# Enclosure_85x58_BHWSL.net
KiCad netlist of a schematic drawn in EAGLE
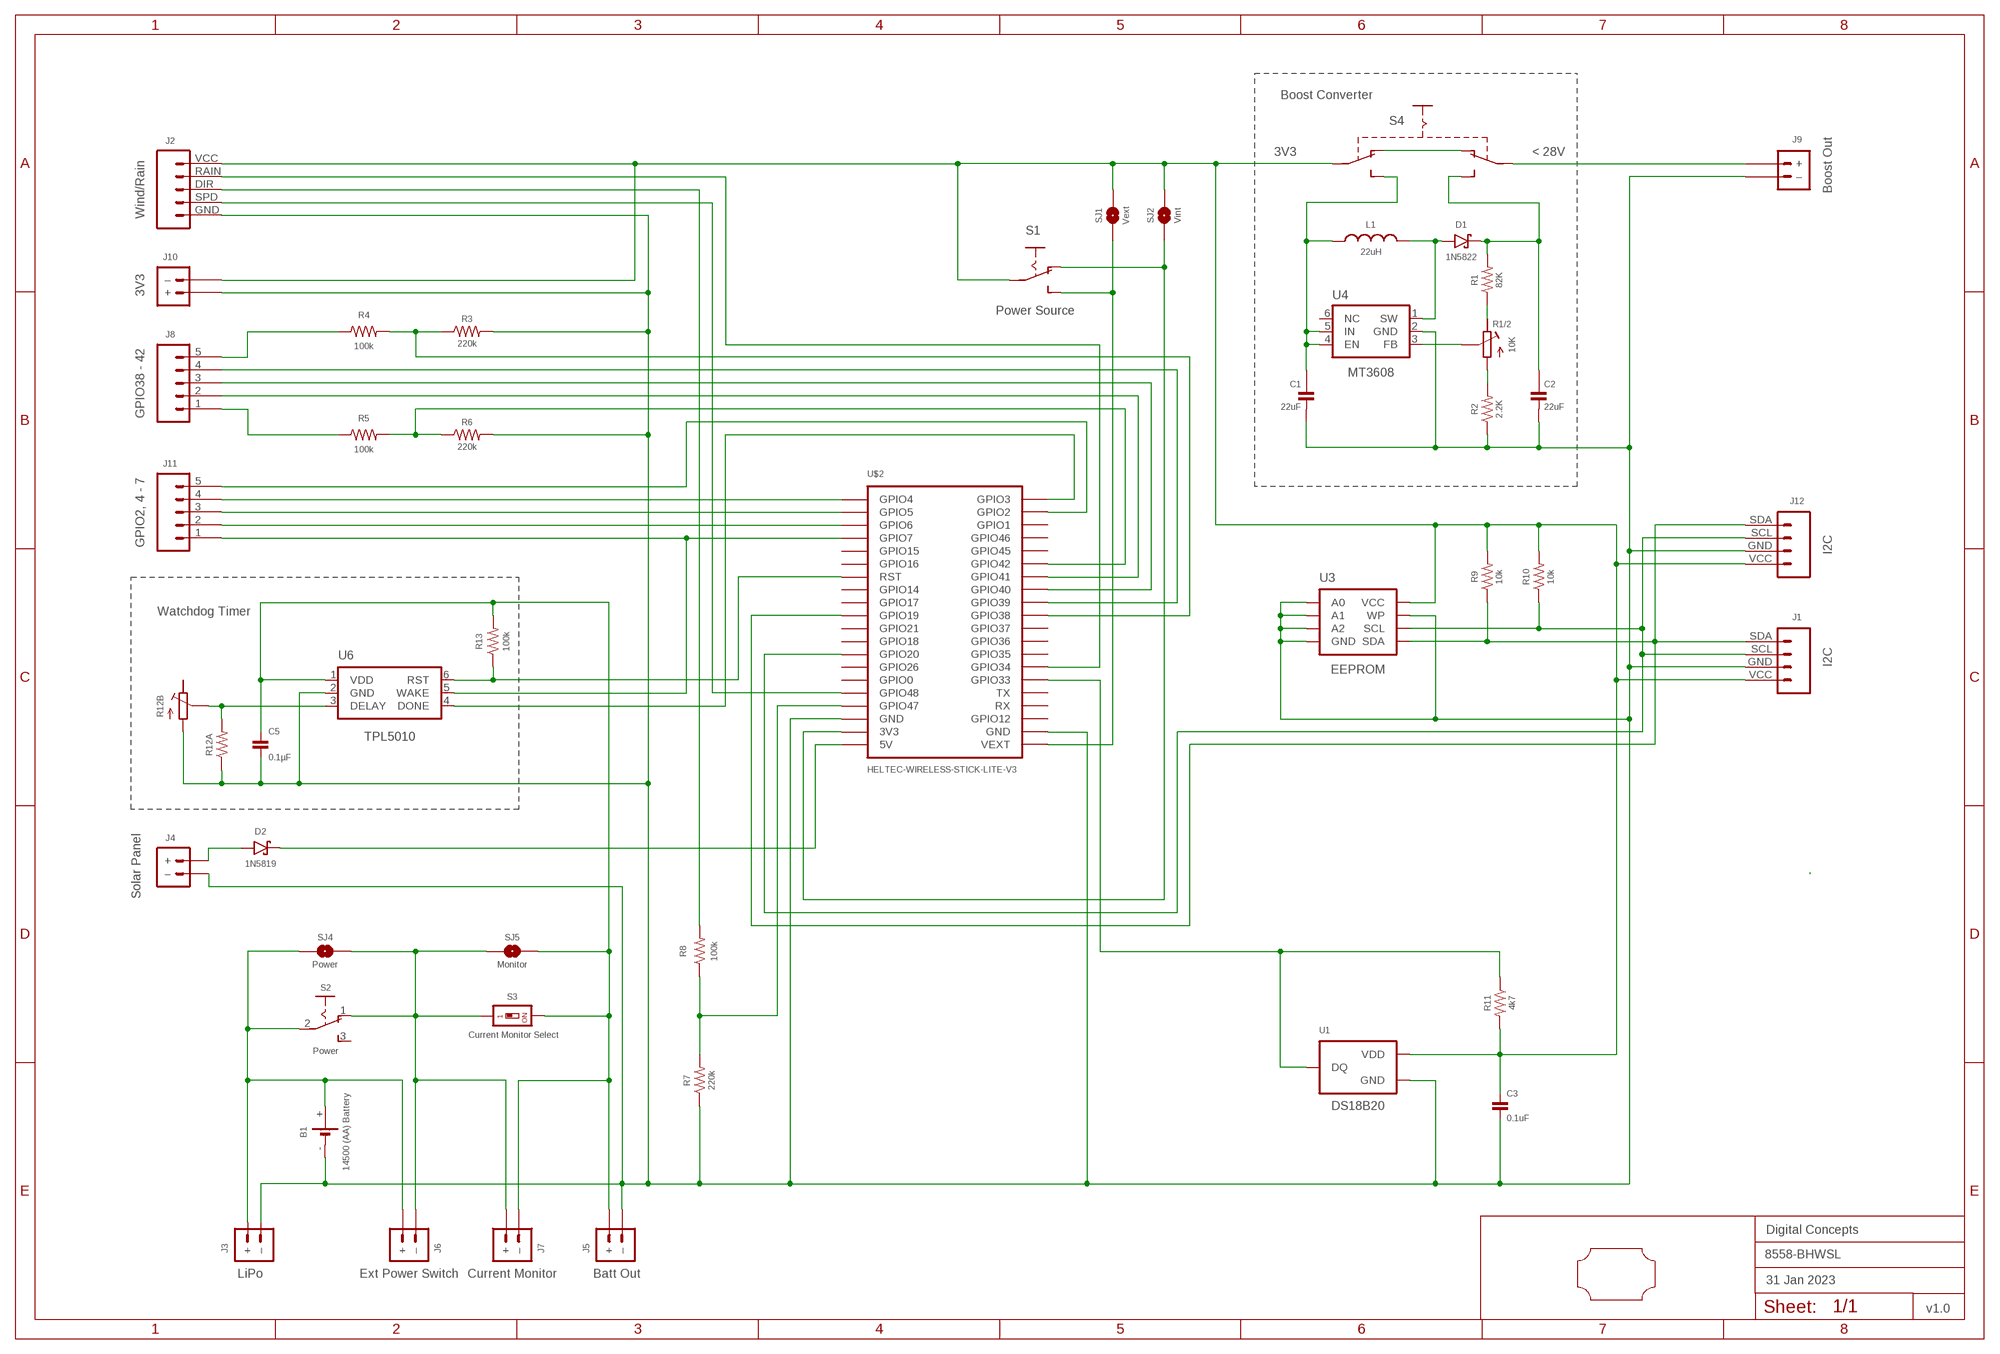
[diagram p0: schematic, sheet 1]

(export (version "E")
  (design (tool "Eeschema 10.0.6"))
  (components
    (comp (ref "B1")
      (value "14500 (AA) Battery")
      (footprint "eagle-import:BATTERY-14500")
      (libsource (lib "eagle-import") (part "BATTERY-HOLDER-14500(AA)"))
    )
    (comp (ref "C1")
      (value "22uF")
      (footprint "eagle-import:C1206")
      (libsource (lib "eagle-import") (part "CAPACITOR-1206"))
    )
    (comp (ref "C2")
      (value "22uF")
      (footprint "eagle-import:C1206")
      (libsource (lib "eagle-import") (part "CAPACITOR-1206"))
    )
    (comp (ref "C3")
      (value "0.1uF")
      (footprint "eagle-import:C0805")
      (libsource (lib "eagle-import") (part "CAPACITOR-0805"))
    )
    (comp (ref "C5")
      (value "0.1µF")
      (footprint "eagle-import:C0805")
      (libsource (lib "eagle-import") (part "CAPACITOR-0805"))
    )
    (comp (ref "D1")
      (value "1N5822")
      (footprint "eagle-import:DIODE_SMB")
      (libsource (lib "eagle-import") (part "DIODE-SCHOTTKY-1N5822"))
    )
    (comp (ref "D2")
      (value "1N5819")
      (footprint "eagle-import:SOD-123")
      (libsource (lib "eagle-import") (part "1N5819-SOD-123"))
    )
    (comp (ref "J1")
      (value "I2C")
      (footprint "eagle-import:JST-PH2.0-4-VERTICAL-I2C")
      (libsource (lib "eagle-import") (part "JST-PH2.0-4-VERTICAL-I2C"))
    )
    (comp (ref "J2")
      (value "Wind/Rain")
      (footprint "eagle-import:JST-PH2.0-5-WEATHER")
      (libsource (lib "eagle-import") (part "JST-PH2.0-5-VERTICAL-WEATHER"))
    )
    (comp (ref "J3")
      (value "LiPo")
      (footprint "eagle-import:JST-PH2.0-2-HORIZONTAL")
      (libsource (lib "eagle-import") (part "JST-PH2.0-2-MALE-HORIZONTALJST-PTH-2"))
    )
    (comp (ref "J4")
      (value "Solar Panel")
      (footprint "eagle-import:JST-PH2.0-2-DUAL-POWER")
      (libsource (lib "eagle-import") (part "JST-PH2.0-2-DUAL-POWERJST-PTH-2"))
    )
    (comp (ref "J5")
      (value "Batt Out")
      (footprint "eagle-import:JST-GH1.25-2-HORIZONTAL")
      (libsource (lib "eagle-import") (part "JST-GH1.25-2-HORIZONTAL-POWER"))
    )
    (comp (ref "J6")
      (value "Ext Power Switch")
      (footprint "eagle-import:JST-PH2.0-2-DUAL-POWER")
      (libsource (lib "eagle-import") (part "JST-PH2.0-2-DUAL-POWERJST-PTH-2"))
    )
    (comp (ref "J7")
      (value "Current Monitor")
      (footprint "eagle-import:JST-PH2.0-2-HORIZONTAL-POWER@1")
      (libsource (lib "eagle-import") (part "JST-PH2.0-2-HORIZONTAL-POWERJST-PTH-2"))
    )
    (comp (ref "J8")
      (value "GPIO38 - 42")
      (footprint "eagle-import:JST-PH2.0-5-HORIZONTAL")
      (libsource (lib "eagle-import") (part "JST-PH2.0-5-HORIZONTAL"))
    )
    (comp (ref "J9")
      (value "Boost Out")
      (footprint "eagle-import:JST-PH2.0-2-HORIZONTAL-POWER")
      (libsource (lib "eagle-import") (part "JST-PH2.0-2-H-POWER"))
    )
    (comp (ref "J10")
      (value "3V3")
      (footprint "eagle-import:JST-PH2.0-2-HORIZONTAL-POWER")
      (libsource (lib "eagle-import") (part "JST-PH2.0-2-H-POWER"))
    )
    (comp (ref "J11")
      (value "GPIO2, 4 - 7")
      (footprint "eagle-import:JST-PH2.0-5-HORIZONTAL")
      (libsource (lib "eagle-import") (part "JST-PH2.0-5-HORIZONTAL"))
    )
    (comp (ref "J12")
      (value "I2C")
      (footprint "eagle-import:JST-PH2.0-4-HORIZONTAL-I2C")
      (libsource (lib "eagle-import") (part "JST-PH2.0-4-HORIZONTAL-I2C"))
    )
    (comp (ref "L1")
      (value "22uH")
      (footprint "eagle-import:CDRH104R+6D28")
      (libsource (lib "eagle-import") (part "INDUCTOR-CDRH104R/6D28L5038P"))
    )
    (comp (ref "R1")
      (value "82K")
      (footprint "eagle-import:R0805")
      (libsource (lib "eagle-import") (part "RESISTORR0805"))
    )
    (comp (ref "R1/2")
      (value "10K")
      (footprint "eagle-import:RTRIM64P")
      (libsource (lib "eagle-import") (part "RESISTOR-TRIMM-BAOTER-HORIZONTAL"))
    )
    (comp (ref "R2")
      (value "2.2K")
      (footprint "eagle-import:R0805")
      (libsource (lib "eagle-import") (part "RESISTORR0805"))
    )
    (comp (ref "R3")
      (value "220k")
      (footprint "eagle-import:R0805")
      (libsource (lib "eagle-import") (part "RESISTORR0805"))
    )
    (comp (ref "R4")
      (value "100k")
      (footprint "eagle-import:R0805")
      (libsource (lib "eagle-import") (part "RESISTORR0805"))
    )
    (comp (ref "R5")
      (value "100k")
      (footprint "eagle-import:R0805")
      (libsource (lib "eagle-import") (part "RESISTORR0805"))
    )
    (comp (ref "R6")
      (value "220k")
      (footprint "eagle-import:R0805")
      (libsource (lib "eagle-import") (part "RESISTORR0805"))
    )
    (comp (ref "R7")
      (value "220k")
      (footprint "eagle-import:R0805")
      (libsource (lib "eagle-import") (part "RESISTORR0805"))
    )
    (comp (ref "R8")
      (value "100k")
      (footprint "eagle-import:R0805")
      (libsource (lib "eagle-import") (part "RESISTORR0805"))
    )
    (comp (ref "R9")
      (value "10k")
      (footprint "eagle-import:R0805")
      (libsource (lib "eagle-import") (part "RESISTORR0805"))
    )
    (comp (ref "R10")
      (value "10k")
      (footprint "eagle-import:R0805")
      (libsource (lib "eagle-import") (part "RESISTORR0805"))
    )
    (comp (ref "R11")
      (value "4k7")
      (footprint "eagle-import:R0805")
      (libsource (lib "eagle-import") (part "RESISTORR0805"))
    )
    (comp (ref "R12A")
      (value "RESISTORR0805")
      (footprint "eagle-import:R0805")
      (libsource (lib "eagle-import") (part "RESISTORR0805"))
    )
    (comp (ref "R12B")
      (value "RESISTOR-TRIMM-33")
      (footprint "eagle-import:RTRIM3_3")
      (libsource (lib "eagle-import") (part "RESISTOR-TRIMM-33"))
    )
    (comp (ref "R13")
      (value "100k")
      (footprint "eagle-import:R0805")
      (libsource (lib "eagle-import") (part "RESISTORR0805"))
    )
    (comp (ref "S1")
      (value "Power Source")
      (footprint "eagle-import:SWITCH-SPDT-SMT")
      (libsource (lib "eagle-import") (part "SWITCH-SLIDE-SPDT-SMT"))
    )
    (comp (ref "S2")
      (value "Power")
      (footprint "eagle-import:SWITCH-SLIDE-SPDT")
      (libsource (lib "eagle-import") (part "SWITCH-SLIDE-SPDT"))
    )
    (comp (ref "S3")
      (value "Current Monitor Select")
      (footprint "eagle-import:SMD-001")
      (libsource (lib "eagle-import") (part "SWITCH-DIP-SWS001"))
    )
    (comp (ref "S4")
      (value "SWITCH-SLIDE-DPDT-PTH-S")
      (footprint "eagle-import:SWITCH-DPDT-PTH")
      (libsource (lib "eagle-import") (part "SWITCH-SLIDE-DPDT-PTH-S"))
    )
    (comp (ref "SJ1")
      (value "Vext")
      (footprint "eagle-import:SJ")
      (libsource (lib "eagle-import") (part "SJ"))
    )
    (comp (ref "SJ2")
      (value "Vint")
      (footprint "eagle-import:SJ-VIA-1")
      (libsource (lib "eagle-import") (part "SJ-V-1"))
    )
    (comp (ref "SJ4")
      (value "Power")
      (footprint "eagle-import:SJ")
      (libsource (lib "eagle-import") (part "SJ"))
    )
    (comp (ref "SJ5")
      (value "Monitor")
      (footprint "eagle-import:SJ")
      (libsource (lib "eagle-import") (part "SJ"))
    )
    (comp (ref "U$1")
      (value "PCB-OUTLINE-85X58")
      (footprint "eagle-import:PROTO-28X18-OUTLINE")
      (libsource (lib "eagle-import") (part "PCB-OUTLINE-85X58"))
    )
    (comp (ref "U$2")
      (value "HELTEC-WIRELESS-STICK-LITE-V3")
      (footprint "eagle-import:HELTEC-WIRELESS-STICK-LITE-V3")
      (libsource (lib "eagle-import") (part "HELTEC-WIRELESS-STICK-LITE-V3"))
    )
    (comp (ref "U1")
      (value "DS18B20")
      (footprint "eagle-import:TO-92")
      (fields (field (name "MF") "Maxim Integrated"))
      (libsource (lib "eagle-import") (part "THERMOMETER-DS18B20"))
    )
    (comp (ref "U3")
      (value "EEPROM")
      (footprint "eagle-import:SOP-8")
      (libsource (lib "eagle-import") (part "AT24CXX-EEPROM"))
    )
    (comp (ref "U4")
      (value "MT3608")
      (footprint "eagle-import:SOT-23-6@1")
      (libsource (lib "eagle-import") (part "MT3608"))
    )
    (comp (ref "U6")
      (value "TPL5010")
      (footprint "eagle-import:SOT-23-6")
      (libsource (lib "eagle-import") (part "TPL5010DDCR"))
    )
  )
  (nets
    (net (code "1") (name "Net-(D2-PadA)") (class "Default")
      (node (ref "D2") (pin "A") (pinfunction "A_A") (pintype "passive"))
      (node (ref "J4") (pin "+") (pinfunction "+_+") (pintype "power_in"))
    )
    (net (code "2") (name "Net-(D2-PadC)") (class "Default")
      (node (ref "D2") (pin "C") (pinfunction "C_C") (pintype "passive"))
      (node (ref "U$2") (pin "5V") (pinfunction "5V_5V") (pintype "bidirectional"))
    )
    (net (code "3") (name "Net-(J1-1)") (class "Default")
      (node (ref "J1") (pin "SDA") (pinfunction "1_SDA") (pintype "passive"))
      (node (ref "J12") (pin "SDA") (pinfunction "1_SDA") (pintype "passive"))
      (node (ref "R9") (pin "1") (pinfunction "1_1") (pintype "passive"))
      (node (ref "U$2") (pin "GPIO19") (pinfunction "GPIO19_GPIO19") (pintype "bidirectional"))
      (node (ref "U3") (pin "P$5") (pinfunction "SDA_P$5") (pintype "bidirectional"))
    )
    (net (code "4") (name "Net-(J1-2)") (class "Default")
      (node (ref "J1") (pin "SCL") (pinfunction "2_SCL") (pintype "passive"))
      (node (ref "J12") (pin "SCL") (pinfunction "2_SCL") (pintype "passive"))
      (node (ref "R10") (pin "1") (pinfunction "1_1") (pintype "passive"))
      (node (ref "U$2") (pin "GPIO20") (pinfunction "GPIO20_GPIO20") (pintype "bidirectional"))
      (node (ref "U3") (pin "P$6") (pinfunction "SCL_P$6") (pintype "bidirectional"))
    )
    (net (code "5") (name "Net-(J1-3)") (class "Default")
      (node (ref "B1") (pin "-") (pinfunction "-_-") (pintype "power_in"))
      (node (ref "C1") (pin "2") (pinfunction "2_2") (pintype "passive"))
      (node (ref "C2") (pin "2") (pinfunction "2_2") (pintype "passive"))
      (node (ref "C3") (pin "2") (pinfunction "2_2") (pintype "passive"))
      (node (ref "C5") (pin "2") (pinfunction "2_2") (pintype "passive"))
      (node (ref "J1") (pin "GND") (pinfunction "3_GND") (pintype "passive"))
      (node (ref "J10") (pin "+") (pinfunction "+_+") (pintype "power_in"))
      (node (ref "J12") (pin "GND") (pinfunction "3_GND") (pintype "passive"))
      (node (ref "J2") (pin "GND") (pinfunction "5_GND") (pintype "passive"))
      (node (ref "J3") (pin "-") (pinfunction "–_-") (pintype "power_in"))
      (node (ref "J4") (pin "-") (pinfunction "–_-") (pintype "power_in"))
      (node (ref "J5") (pin "-") (pinfunction "–_-") (pintype "power_in"))
      (node (ref "J9") (pin "-") (pinfunction "–_-") (pintype "power_in"))
      (node (ref "R12A") (pin "1") (pinfunction "1_1") (pintype "passive"))
      (node (ref "R12B") (pin "1") (pinfunction "A_1") (pintype "passive"))
      (node (ref "R2") (pin "1") (pinfunction "1_1") (pintype "passive"))
      (node (ref "R3") (pin "2") (pinfunction "2_2") (pintype "passive"))
      (node (ref "R6") (pin "2") (pinfunction "2_2") (pintype "passive"))
      (node (ref "R7") (pin "1") (pinfunction "1_1") (pintype "passive"))
      (node (ref "U$2") (pin "GND@18") (pinfunction "GND_GND@18") (pintype "bidirectional"))
      (node (ref "U$2") (pin "GND@22") (pinfunction "GND_GND@22") (pintype "bidirectional"))
      (node (ref "U1") (pin "1") (pinfunction "GND_1") (pintype "power_in"))
      (node (ref "U3") (pin "P$1") (pinfunction "A0_P$1") (pintype "bidirectional"))
      (node (ref "U3") (pin "P$2") (pinfunction "A1_P$2") (pintype "bidirectional"))
      (node (ref "U3") (pin "P$3") (pinfunction "A2_P$3") (pintype "bidirectional"))
      (node (ref "U3") (pin "P$4") (pinfunction "GND_P$4") (pintype "bidirectional"))
      (node (ref "U3") (pin "P$7") (pinfunction "WP_P$7") (pintype "bidirectional"))
      (node (ref "U4") (pin "2") (pinfunction "GND_2") (pintype "power_in"))
      (node (ref "U6") (pin "2") (pinfunction "GND_2") (pintype "power_in"))
    )
    (net (code "6") (name "Net-(J1-4)") (class "Default")
      (node (ref "C3") (pin "1") (pinfunction "1_1") (pintype "passive"))
      (node (ref "J1") (pin "VCC") (pinfunction "4_VCC") (pintype "passive"))
      (node (ref "J10") (pin "-") (pinfunction "–_-") (pintype "power_in"))
      (node (ref "J12") (pin "VCC") (pinfunction "4_VCC") (pintype "passive"))
      (node (ref "J2") (pin "VCC") (pinfunction "1_VCC") (pintype "passive"))
      (node (ref "R10") (pin "2") (pinfunction "2_2") (pintype "passive"))
      (node (ref "R11") (pin "2") (pinfunction "2_2") (pintype "passive"))
      (node (ref "R9") (pin "2") (pinfunction "2_2") (pintype "passive"))
      (node (ref "S1") (pin "COMMON") (pinfunction "P_COMMON") (pintype "passive"))
      (node (ref "S4") (pin "P$5") (pinfunction "P2_P$5") (pintype "passive"))
      (node (ref "SJ1") (pin "1") (pinfunction "1_1") (pintype "passive"))
      (node (ref "SJ2") (pin "1") (pinfunction "1_1") (pintype "passive"))
      (node (ref "SJ2") (pin "1@V") (pinfunction "1_1@V") (pintype "passive"))
      (node (ref "U1") (pin "3") (pinfunction "VDD_3") (pintype "power_in"))
      (node (ref "U3") (pin "P$8") (pinfunction "VCC_P$8") (pintype "bidirectional"))
    )
    (net (code "7") (name "Net-(J2-2)") (class "Default")
      (node (ref "J2") (pin "RAIN") (pinfunction "2_RAIN") (pintype "passive"))
      (node (ref "U$2") (pin "GPIO34") (pinfunction "GPIO34_GPIO34") (pintype "bidirectional"))
    )
    (net (code "8") (name "Net-(J2-3)") (class "Default")
      (node (ref "J2") (pin "DIR") (pinfunction "3_DIR") (pintype "passive"))
      (node (ref "R8") (pin "2") (pinfunction "2_2") (pintype "passive"))
    )
    (net (code "9") (name "Net-(J2-4)") (class "Default")
      (node (ref "J2") (pin "SPD") (pinfunction "4_SPD") (pintype "passive"))
      (node (ref "U$2") (pin "GPIO48") (pinfunction "GPIO48_GPIO48") (pintype "bidirectional"))
    )
    (net (code "10") (name "Net-(J6-–)") (class "Default")
      (node (ref "J6") (pin "-") (pinfunction "–_-") (pintype "power_in"))
      (node (ref "J7") (pin "+") (pinfunction "+_+") (pintype "power_in"))
      (node (ref "S2") (pin "1") (pinfunction "O_1") (pintype "passive"))
      (node (ref "S3") (pin "1") (pinfunction "1_1") (pintype "passive"))
      (node (ref "SJ4") (pin "1") (pinfunction "1_1") (pintype "passive"))
      (node (ref "SJ5") (pin "2") (pinfunction "2_2") (pintype "passive"))
    )
    (net (code "11") (name "Net-(J7-–)") (class "Default")
      (node (ref "C5") (pin "1") (pinfunction "1_1") (pintype "passive"))
      (node (ref "J5") (pin "+") (pinfunction "+_+") (pintype "power_in"))
      (node (ref "J7") (pin "-") (pinfunction "–_-") (pintype "power_in"))
      (node (ref "R13") (pin "2") (pinfunction "2_2") (pintype "passive"))
      (node (ref "S3") (pin "2") (pinfunction "2_2") (pintype "passive"))
      (node (ref "SJ5") (pin "1") (pinfunction "1_1") (pintype "passive"))
      (node (ref "U6") (pin "1") (pinfunction "VDD_1") (pintype "power_in"))
    )
    (net (code "12") (name "Net-(J8-Pad1)") (class "Default")
      (node (ref "J8") (pin "1") (pinfunction "1_1") (pintype "passive"))
      (node (ref "R5") (pin "1") (pinfunction "1_1") (pintype "passive"))
    )
    (net (code "13") (name "Net-(J8-Pad2)") (class "Default")
      (node (ref "J8") (pin "2") (pinfunction "2_2") (pintype "passive"))
      (node (ref "U$2") (pin "GPIO41") (pinfunction "GPIO41_GPIO41") (pintype "bidirectional"))
    )
    (net (code "14") (name "Net-(J8-Pad3)") (class "Default")
      (node (ref "J8") (pin "3") (pinfunction "3_3") (pintype "passive"))
      (node (ref "U$2") (pin "GPIO40") (pinfunction "GPIO40_GPIO40") (pintype "bidirectional"))
    )
    (net (code "15") (name "Net-(J8-Pad4)") (class "Default")
      (node (ref "J8") (pin "4") (pinfunction "4_4") (pintype "passive"))
      (node (ref "U$2") (pin "GPIO39") (pinfunction "GPIO39_GPIO39") (pintype "bidirectional"))
    )
    (net (code "16") (name "Net-(J8-Pad5)") (class "Default")
      (node (ref "J8") (pin "5") (pinfunction "5_5") (pintype "passive"))
      (node (ref "R4") (pin "1") (pinfunction "1_1") (pintype "passive"))
    )
    (net (code "17") (name "Net-(J11-Pad2)") (class "Default")
      (node (ref "J11") (pin "2") (pinfunction "2_2") (pintype "passive"))
      (node (ref "U$2") (pin "GPIO6") (pinfunction "GPIO6_GPIO6") (pintype "bidirectional"))
    )
    (net (code "18") (name "Net-(J11-Pad3)") (class "Default")
      (node (ref "J11") (pin "3") (pinfunction "3_3") (pintype "passive"))
      (node (ref "U$2") (pin "GPIO5") (pinfunction "GPIO5_GPIO5") (pintype "bidirectional"))
    )
    (net (code "19") (name "Net-(J11-Pad4)") (class "Default")
      (node (ref "J11") (pin "4") (pinfunction "4_4") (pintype "passive"))
      (node (ref "U$2") (pin "GPIO4") (pinfunction "GPIO4_GPIO4") (pintype "bidirectional"))
    )
    (net (code "20") (name "Net-(J11-Pad5)") (class "Default")
      (node (ref "J11") (pin "5") (pinfunction "5_5") (pintype "passive"))
      (node (ref "U$2") (pin "GPIO2") (pinfunction "GPIO2_GPIO2") (pintype "bidirectional"))
    )
    (net (code "21") (name "Net-(R1/2-A)") (class "Default")
      (node (ref "R1/2") (pin "1") (pinfunction "A_1") (pintype "passive"))
      (node (ref "R2") (pin "2") (pinfunction "2_2") (pintype "passive"))
    )
    (net (code "22") (name "Net-(R1/2-E)") (class "Default")
      (node (ref "R1") (pin "1") (pinfunction "1_1") (pintype "passive"))
      (node (ref "R1/2") (pin "3") (pinfunction "E_3") (pintype "passive"))
    )
    (net (code "23") (name "Net-(R1/2-S)") (class "Default")
      (node (ref "R1/2") (pin "2") (pinfunction "S_2") (pintype "passive"))
      (node (ref "U4") (pin "3") (pinfunction "FB_3") (pintype "input"))
    )
    (net (code "24") (name "Net-(R3-Pad1)") (class "Default")
      (node (ref "R3") (pin "1") (pinfunction "1_1") (pintype "passive"))
      (node (ref "R4") (pin "2") (pinfunction "2_2") (pintype "passive"))
      (node (ref "U$2") (pin "GPIO38") (pinfunction "GPIO38_GPIO38") (pintype "bidirectional"))
    )
    (net (code "25") (name "Net-(R5-Pad2)") (class "Default")
      (node (ref "R5") (pin "2") (pinfunction "2_2") (pintype "passive"))
      (node (ref "R6") (pin "1") (pinfunction "1_1") (pintype "passive"))
      (node (ref "U$2") (pin "GPIO42") (pinfunction "GPIO42_GPIO42") (pintype "bidirectional"))
    )
    (net (code "26") (name "Net-(R7-Pad2)") (class "Default")
      (node (ref "R7") (pin "2") (pinfunction "2_2") (pintype "passive"))
      (node (ref "R8") (pin "1") (pinfunction "1_1") (pintype "passive"))
      (node (ref "U$2") (pin "GPIO47") (pinfunction "GPIO47_GPIO47") (pintype "bidirectional"))
    )
    (net (code "27") (name "Net-(R12B-S)") (class "Default")
      (node (ref "R12A") (pin "2") (pinfunction "2_2") (pintype "passive"))
      (node (ref "R12B") (pin "2") (pinfunction "S_2") (pintype "passive"))
      (node (ref "U6") (pin "3") (pinfunction "DELAY_3") (pintype "input"))
    )
    (net (code "28") (name "Net-(S1-O)") (class "Default")
      (node (ref "S1") (pin "P$1") (pinfunction "O_P$1") (pintype "passive"))
      (node (ref "SJ2") (pin "2") (pinfunction "2_2") (pintype "passive"))
      (node (ref "U$2") (pin "3V3") (pinfunction "3V3_3V3") (pintype "bidirectional"))
    )
    (net (code "29") (name "Net-(S1-S)") (class "Default")
      (node (ref "S1") (pin "P$2") (pinfunction "S_P$2") (pintype "passive"))
      (node (ref "SJ1") (pin "2") (pinfunction "2_2") (pintype "passive"))
      (node (ref "U$2") (pin "VEXT") (pinfunction "VEXT_VEXT") (pintype "bidirectional"))
    )
    (net (code "30") (name "Net-(S2-P)") (class "Default")
      (node (ref "B1") (pin "+") (pinfunction "+_+") (pintype "power_in"))
      (node (ref "J3") (pin "+") (pinfunction "+_+") (pintype "power_in"))
      (node (ref "J6") (pin "+") (pinfunction "+_+") (pintype "power_in"))
      (node (ref "S2") (pin "2") (pinfunction "P_2") (pintype "passive"))
      (node (ref "SJ4") (pin "2") (pinfunction "2_2") (pintype "passive"))
    )
    (net (code "31") (name "Net-(S4-O1)") (class "Default")
      (node (ref "S4") (pin "P$1") (pinfunction "O1_P$1") (pintype "passive"))
      (node (ref "S4") (pin "P$4") (pinfunction "O2_P$4") (pintype "passive"))
    )
    (net (code "32") (name "Net-(S4-P1)") (class "Default")
      (node (ref "J9") (pin "+") (pinfunction "+_+") (pintype "power_in"))
      (node (ref "S4") (pin "P$2") (pinfunction "P1_P$2") (pintype "passive"))
    )
    (net (code "33") (name "Net-(S4-S1)") (class "Default")
      (node (ref "C2") (pin "1") (pinfunction "1_1") (pintype "passive"))
      (node (ref "D1") (pin "C") (pinfunction "C_C") (pintype "passive"))
      (node (ref "R1") (pin "2") (pinfunction "2_2") (pintype "passive"))
      (node (ref "S4") (pin "P$3") (pinfunction "S1_P$3") (pintype "passive"))
    )
    (net (code "34") (name "Net-(S4-S2)") (class "Default")
      (node (ref "C1") (pin "1") (pinfunction "1_1") (pintype "passive"))
      (node (ref "L1") (pin "2") (pinfunction "2_2") (pintype "passive"))
      (node (ref "S4") (pin "P$6") (pinfunction "S2_P$6") (pintype "passive"))
      (node (ref "U4") (pin "4") (pinfunction "EN_4") (pintype "input"))
      (node (ref "U4") (pin "5") (pinfunction "IN_5") (pintype "power_in"))
    )
    (net (code "35") (name "Net-(U1-DQ)") (class "Default")
      (node (ref "R11") (pin "1") (pinfunction "1_1") (pintype "passive"))
      (node (ref "U$2") (pin "GPIO33") (pinfunction "GPIO33_GPIO33") (pintype "bidirectional"))
      (node (ref "U1") (pin "2") (pinfunction "DQ_2") (pintype "bidirectional"))
    )
    (net (code "36") (name "Net-(U4-SW)") (class "Default")
      (node (ref "D1") (pin "A") (pinfunction "A_A") (pintype "passive"))
      (node (ref "L1") (pin "1") (pinfunction "1_1") (pintype "passive"))
      (node (ref "U4") (pin "1") (pinfunction "SW_1") (pintype "power_in"))
    )
    (net (code "37") (name "Net-(U6-DONE)") (class "Default")
      (node (ref "U$2") (pin "GPIO3") (pinfunction "GPIO3_GPIO3") (pintype "bidirectional"))
      (node (ref "U6") (pin "4") (pinfunction "DONE_4") (pintype "input"))
    )
    (net (code "38") (name "Net-(U6-RST)") (class "Default")
      (node (ref "R13") (pin "1") (pinfunction "1_1") (pintype "passive"))
      (node (ref "U$2") (pin "RST") (pinfunction "RST_RST") (pintype "bidirectional"))
      (node (ref "U6") (pin "6") (pinfunction "RST_6") (pintype "output"))
    )
    (net (code "39") (name "Net-(U6-WAKE)") (class "Default")
      (node (ref "J11") (pin "1") (pinfunction "1_1") (pintype "passive"))
      (node (ref "U$2") (pin "GPIO7") (pinfunction "GPIO7_GPIO7") (pintype "bidirectional"))
      (node (ref "U6") (pin "5") (pinfunction "WAKE_5") (pintype "output"))
    )
    (net (code "40") (name "unconnected-(R12B-E-Pad3)") (class "Default")
      (node (ref "R12B") (pin "3") (pinfunction "E_3") (pintype "passive"))
    )
    (net (code "41") (name "unconnected-(S2-S-Pad3)") (class "Default")
      (node (ref "S2") (pin "3") (pinfunction "S_3") (pintype "passive"))
    )
    (net (code "42") (name "unconnected-(U$2-PadGPIO0)") (class "Default")
      (node (ref "U$2") (pin "GPIO0") (pinfunction "GPIO0_GPIO0") (pintype "bidirectional"))
    )
    (net (code "43") (name "unconnected-(U$2-PadGPIO1)") (class "Default")
      (node (ref "U$2") (pin "GPIO1") (pinfunction "GPIO1_GPIO1") (pintype "bidirectional"))
    )
    (net (code "44") (name "unconnected-(U$2-PadGPIO12)") (class "Default")
      (node (ref "U$2") (pin "GPIO12") (pinfunction "GPIO12_GPIO12") (pintype "bidirectional"))
    )
    (net (code "45") (name "unconnected-(U$2-PadGPIO14)") (class "Default")
      (node (ref "U$2") (pin "GPIO14") (pinfunction "GPIO14_GPIO14") (pintype "bidirectional"))
    )
    (net (code "46") (name "unconnected-(U$2-PadGPIO15)") (class "Default")
      (node (ref "U$2") (pin "GPIO15") (pinfunction "GPIO15_GPIO15") (pintype "bidirectional"))
    )
    (net (code "47") (name "unconnected-(U$2-PadGPIO16)") (class "Default")
      (node (ref "U$2") (pin "GPIO16") (pinfunction "GPIO16_GPIO16") (pintype "bidirectional"))
    )
    (net (code "48") (name "unconnected-(U$2-PadGPIO17)") (class "Default")
      (node (ref "U$2") (pin "GPIO17") (pinfunction "GPIO17_GPIO17") (pintype "bidirectional"))
    )
    (net (code "49") (name "unconnected-(U$2-PadGPIO18)") (class "Default")
      (node (ref "U$2") (pin "GPIO18") (pinfunction "GPIO18_GPIO18") (pintype "bidirectional"))
    )
    (net (code "50") (name "unconnected-(U$2-PadGPIO21)") (class "Default")
      (node (ref "U$2") (pin "GPIO21") (pinfunction "GPIO21_GPIO21") (pintype "bidirectional"))
    )
    (net (code "51") (name "unconnected-(U$2-PadGPIO26)") (class "Default")
      (node (ref "U$2") (pin "GPIO26") (pinfunction "GPIO26_GPIO26") (pintype "bidirectional"))
    )
    (net (code "52") (name "unconnected-(U$2-PadGPIO35)") (class "Default")
      (node (ref "U$2") (pin "GPIO35") (pinfunction "GPIO35_GPIO35") (pintype "bidirectional"))
    )
    (net (code "53") (name "unconnected-(U$2-PadGPIO36)") (class "Default")
      (node (ref "U$2") (pin "GPIO36") (pinfunction "GPIO36_GPIO36") (pintype "bidirectional"))
    )
    (net (code "54") (name "unconnected-(U$2-PadGPIO37)") (class "Default")
      (node (ref "U$2") (pin "GPIO37") (pinfunction "GPIO37_GPIO37") (pintype "bidirectional"))
    )
    (net (code "55") (name "unconnected-(U$2-PadGPIO45)") (class "Default")
      (node (ref "U$2") (pin "GPIO45") (pinfunction "GPIO45_GPIO45") (pintype "bidirectional"))
    )
    (net (code "56") (name "unconnected-(U$2-PadGPIO46)") (class "Default")
      (node (ref "U$2") (pin "GPIO46") (pinfunction "GPIO46_GPIO46") (pintype "bidirectional"))
    )
    (net (code "57") (name "unconnected-(U$2-PadRX)") (class "Default")
      (node (ref "U$2") (pin "RX") (pinfunction "RX_RX") (pintype "bidirectional"))
    )
    (net (code "58") (name "unconnected-(U$2-PadTX)") (class "Default")
      (node (ref "U$2") (pin "TX") (pinfunction "TX_TX") (pintype "bidirectional"))
    )
    (net (code "59") (name "unconnected-(U4-NC-Pad6)") (class "Default")
      (node (ref "U4") (pin "6") (pinfunction "NC_6") (pintype "no_connect"))
    )
  )
)
